# Sensor.net
KiCad netlist of a schematic drawn in EAGLE
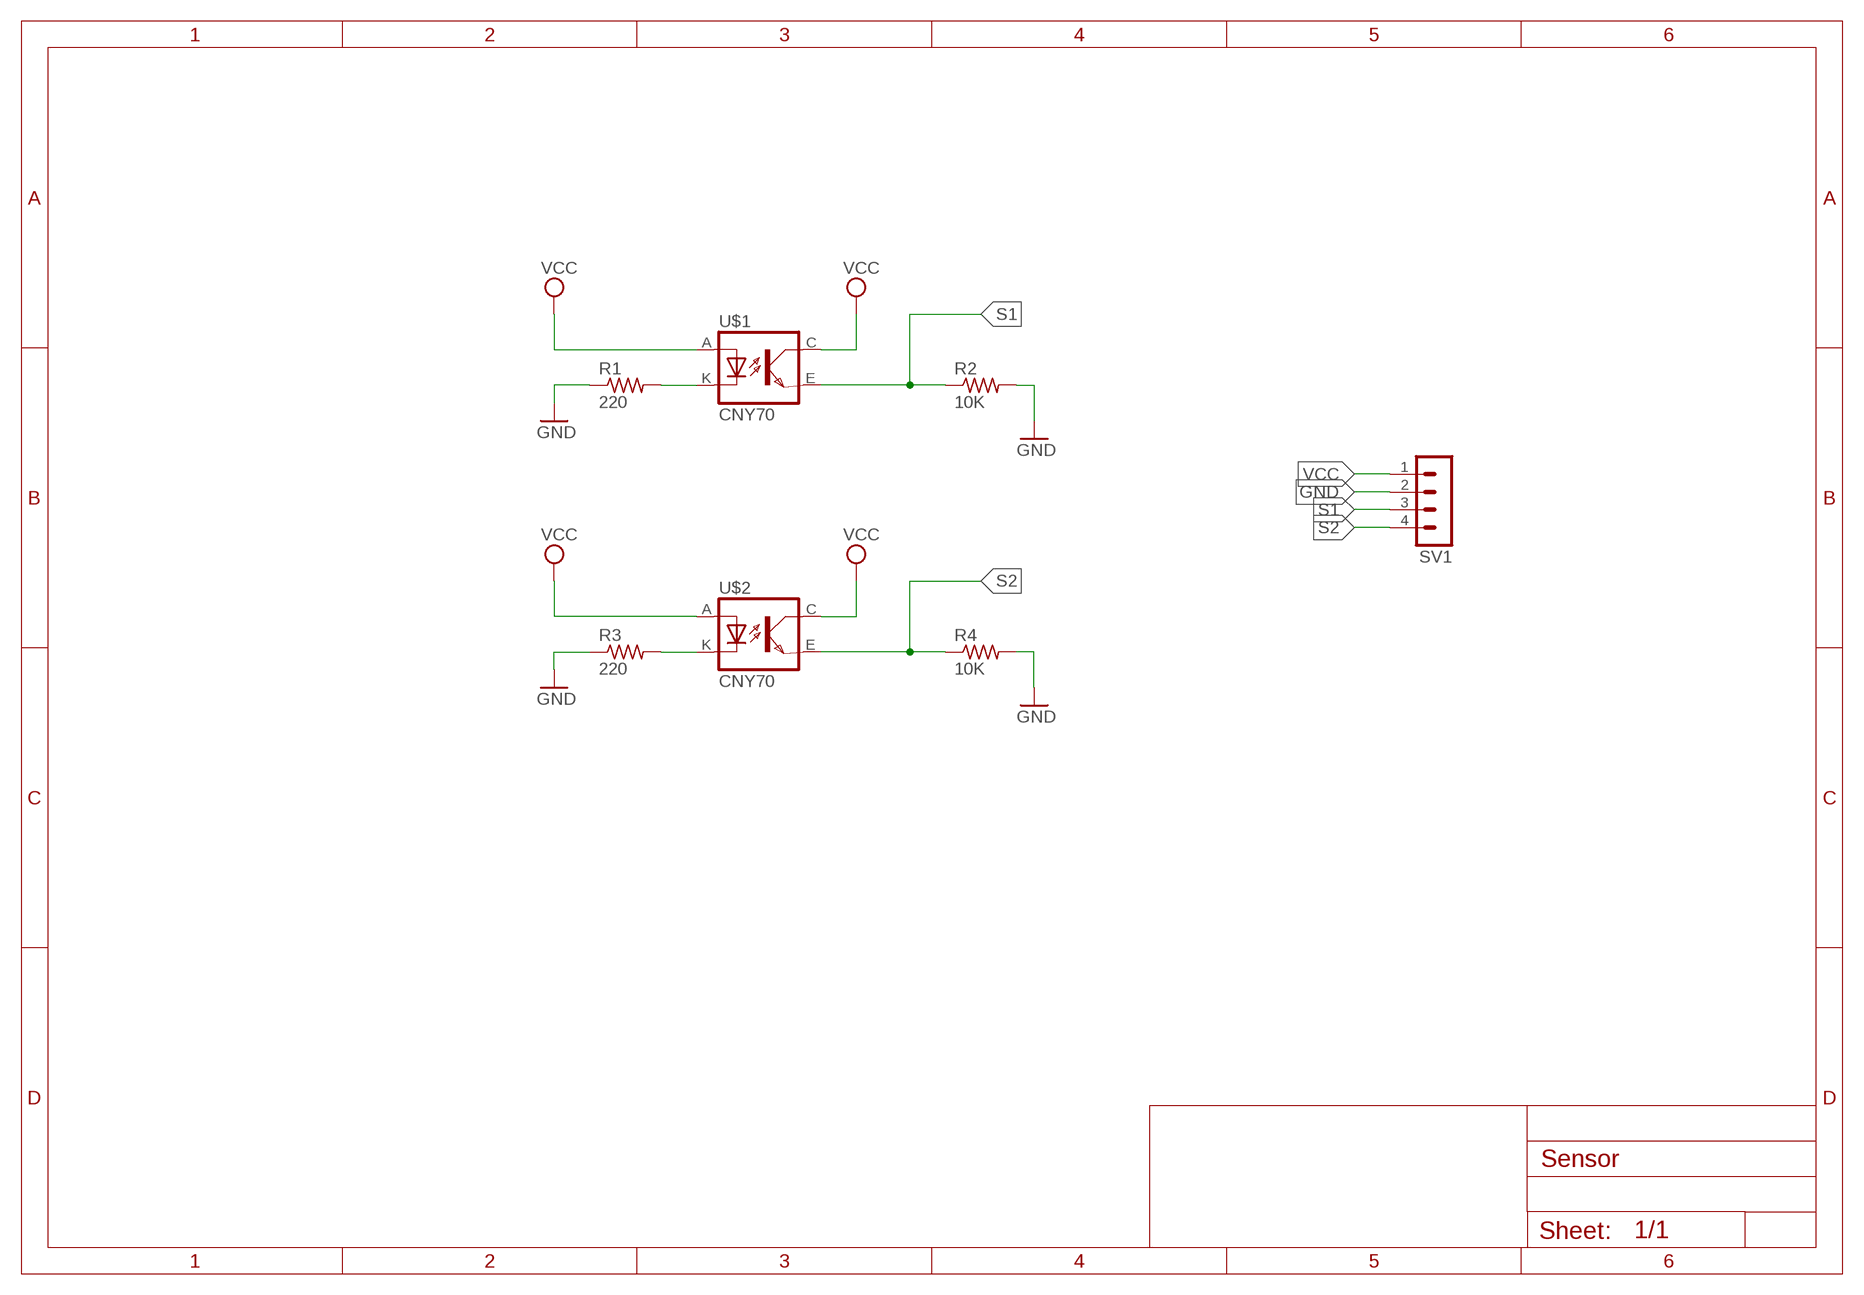
[diagram p0: schematic, sheet 1]

(export (version "E")
  (design (tool "Eeschema 10.0.6"))
  (components
    (comp (ref "R1")
      (value "220")
      (footprint "eagle-import:0207_10")
      (libsource (lib "eagle-import") (part "R-US_0207/10"))
    )
    (comp (ref "R2")
      (value "10K")
      (footprint "eagle-import:0207_10")
      (libsource (lib "eagle-import") (part "R-US_0207/10"))
    )
    (comp (ref "R3")
      (value "220")
      (footprint "eagle-import:0207_10")
      (libsource (lib "eagle-import") (part "R-US_0207/10"))
    )
    (comp (ref "R4")
      (value "10K")
      (footprint "eagle-import:0207_10")
      (libsource (lib "eagle-import") (part "R-US_0207/10"))
    )
    (comp (ref "SV1")
      (value "MA04-1")
      (footprint "eagle-import:MA04-1")
      (libsource (lib "eagle-import") (part "MA04-1"))
    )
    (comp (ref "U$1")
      (value "CNY70")
      (footprint "eagle-import:4")
      (libsource (lib "eagle-import") (part "CNY70"))
    )
    (comp (ref "U$2")
      (value "CNY70")
      (footprint "eagle-import:4")
      (libsource (lib "eagle-import") (part "CNY70"))
    )
  )
  (nets
    (net (code "1") (name "GND") (class "Default")
      (node (ref "R1") (pin "1") (pinfunction "1_1") (pintype "passive"))
      (node (ref "R2") (pin "2") (pinfunction "2_2") (pintype "passive"))
      (node (ref "R3") (pin "1") (pinfunction "1_1") (pintype "passive"))
      (node (ref "R4") (pin "2") (pinfunction "2_2") (pintype "passive"))
      (node (ref "SV1") (pin "2") (pinfunction "2_2") (pintype "passive"))
    )
    (net (code "2") (name "Net-(U$1-C)") (class "Default")
      (node (ref "R1") (pin "2") (pinfunction "2_2") (pintype "passive"))
      (node (ref "U$1") (pin "K") (pinfunction "C_K") (pintype "passive"))
    )
    (net (code "3") (name "Net-(U$2-C)") (class "Default")
      (node (ref "R3") (pin "2") (pinfunction "2_2") (pintype "passive"))
      (node (ref "U$2") (pin "K") (pinfunction "C_K") (pintype "passive"))
    )
    (net (code "4") (name "S1") (class "Default")
      (node (ref "R2") (pin "1") (pinfunction "1_1") (pintype "passive"))
      (node (ref "SV1") (pin "3") (pinfunction "3_3") (pintype "passive"))
      (node (ref "U$1") (pin "E") (pinfunction "EMI_E") (pintype "passive"))
    )
    (net (code "5") (name "S2") (class "Default")
      (node (ref "R4") (pin "1") (pinfunction "1_1") (pintype "passive"))
      (node (ref "SV1") (pin "4") (pinfunction "4_4") (pintype "passive"))
      (node (ref "U$2") (pin "E") (pinfunction "EMI_E") (pintype "passive"))
    )
    (net (code "6") (name "VCC") (class "Default")
      (node (ref "SV1") (pin "1") (pinfunction "1_1") (pintype "passive"))
      (node (ref "U$1") (pin "A") (pinfunction "A_A") (pintype "passive"))
      (node (ref "U$1") (pin "C") (pinfunction "COL_C") (pintype "passive"))
      (node (ref "U$2") (pin "A") (pinfunction "A_A") (pintype "passive"))
      (node (ref "U$2") (pin "C") (pinfunction "COL_C") (pintype "passive"))
    )
  )
)
